# KickTrigger.net
KiCad netlist of a schematic drawn in Altium Designer
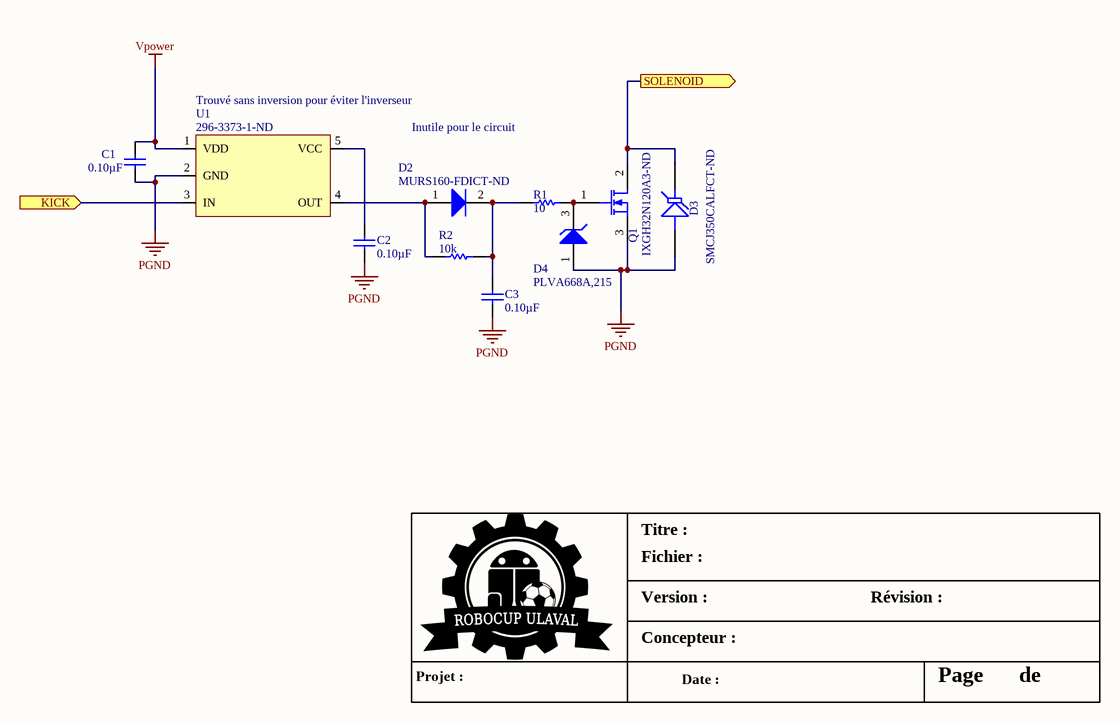
[diagram p0: KickTrigger.SchDoc]

(export (version "E")
  (design (tool "Eeschema 10.0.6"))
  (components
    (comp (ref "C1")
      (value "CL10B104KB8SFNC")
      (footprint "0603")
      (description "CAP CER 0.1UF 50V X7R 0603")
      (fields
        (field (name "MANUFACTURER") "Samsung Electro-Mechanics America, Inc.")
        (field (name "TOLERANCE") "±10%")
        (field (name "CAPACITANCE") "0.10µF")
      )
      (libsource (lib "ResCap") (part "CL10B104KB8SFNC"))
    )
    (comp (ref "C2")
      (value "CL10B104KB8SFNC")
      (footprint "0603")
      (description "CAP CER 0.1UF 50V X7R 0603")
      (fields
        (field (name "MANUFACTURER") "Samsung Electro-Mechanics America, Inc.")
        (field (name "TOLERANCE") "±10%")
        (field (name "CAPACITANCE") "0.10µF")
      )
      (libsource (lib "ResCap") (part "CL10B104KB8SFNC"))
    )
    (comp (ref "C3")
      (value "CL10B104KB8SFNC")
      (footprint "0603")
      (description "CAP CER 0.1UF 50V X7R 0603")
      (fields
        (field (name "MANUFACTURER") "Samsung Electro-Mechanics America, Inc.")
        (field (name "TOLERANCE") "±10%")
        (field (name "CAPACITANCE") "0.10µF")
      )
      (libsource (lib "ResCap") (part "CL10B104KB8SFNC"))
    )
    (comp (ref "D2")
      (value "MURS160-13-F")
      (footprint "SMB")
      (description "DIODE GEN PURP 600V 1A SMB")
      (fields
        (field (name "MANUFACTURER") "Diodes Incorporated")
        (field (name "SUPPLIER PART NUMBER 1") "MURS160-FDICT-ND")
      )
      (libsource (lib "gamma_gestionkicker") (part "MURS160-13-F"))
    )
    (comp (ref "D3")
      (value "SMCJ350CA")
      (footprint "SMC")
      (description "TVS DIODE 350VWM 567VC SMC")
      (fields
        (field (name "MANUFACTURER") "Littelfuse Inc.")
        (field (name "SUPPLIER PART NUMBER 1") "SMCJ350CALFCT-ND")
      )
      (libsource (lib "gamma_gestionkicker") (part "SMCJ350CA"))
    )
    (comp (ref "D4")
      (value "PLVA668A,215")
      (footprint "SOT-23-3")
      (description "DIODE ZENER 6.8V 250MW SOT23")
      (fields (field (name "MANUFACTURER") "NXP Semiconductors") (field (name "TOLERANCE") "±3%"))
      (libsource (lib "gamma_gestionkicker") (part "PLVA668A,215"))
    )
    (comp (ref "Q1")
      (value "IXGH32N120A3")
      (footprint "TO-247 (bent)")
      (description "IGBT 1200V 75A 300W TO247")
      (fields (field (name "MANUFACTURER") "IXYS") (field (name "SUPPLIER PART NUMBER 1") "IXGH32N120A3-ND"))
      (libsource (lib "gamma_gestionkicker") (part "IXGH32N120A3"))
    )
    (comp (ref "R1")
      (value "RC0603FR-0710RL")
      (footprint "0603")
      (description "RES SMD 10 OHM 1% 1/10W 0603")
      (fields
        (field (name "MANUFACTURER") "Yageo")
        (field (name "TOLERANCE") "±1%")
        (field (name "RESISTANCE (OHMS)") "10")
      )
      (libsource (lib "ResCap") (part "RC0603FR-0710RL"))
    )
    (comp (ref "R2")
      (value "RC0603JR-0710KL")
      (footprint "0603")
      (description "RES SMD 10K OHM 5% 1/10W 0603")
      (fields
        (field (name "MANUFACTURER") "Yageo")
        (field (name "TOLERANCE") "±5%")
        (field (name "RESISTANCE (OHMS)") "10k")
      )
      (libsource (lib "ResCap") (part "RC0603JR-0710KL"))
    )
    (comp (ref "U1")
      (value "TPS2818DBVR")
      (footprint "SOT-23-5")
      (description "IC INVERTING FET DRVR SOT-23-5")
      (fields
        (field (name "MANUFACTURER") "Texas Instruments")
        (field (name "SUPPLIER PART NUMBER 1") "296-3373-1-ND")
      )
      (libsource (lib "gamma_gestionkicker") (part "TPS2818DBVR"))
    )
  )
  (nets
    (net (code "1") (name "/KICK") (class "Default")
      (node (ref "U1") (pin "3") (pinfunction "IN_3") (pintype "bidirectional"))
    )
    (net (code "2") (name "/SOLENOID") (class "Default")
      (node (ref "D3") (pin "2") (pinfunction "K_2") (pintype "passive"))
      (node (ref "Q1") (pin "2") (pinfunction "D_2") (pintype "passive"))
    )
    (net (code "3") (name "Net-(D2-A)") (class "Default")
      (node (ref "D2") (pin "1") (pinfunction "A_1") (pintype "passive"))
      (node (ref "R2") (pin "1") (pinfunction "1_1") (pintype "passive"))
      (node (ref "U1") (pin "4") (pinfunction "OUT_4") (pintype "bidirectional"))
    )
    (net (code "4") (name "Net-(D2-K)") (class "Default")
      (node (ref "C3") (pin "2") (pinfunction "2_2") (pintype "passive"))
      (node (ref "D2") (pin "2") (pinfunction "K_2") (pintype "passive"))
      (node (ref "R1") (pin "1") (pinfunction "1_1") (pintype "passive"))
      (node (ref "R2") (pin "2") (pinfunction "2_2") (pintype "passive"))
    )
    (net (code "5") (name "Net-(D4-K)") (class "Default")
      (node (ref "D4") (pin "3") (pinfunction "K_3") (pintype "passive"))
      (node (ref "Q1") (pin "1") (pinfunction "G_1") (pintype "passive"))
      (node (ref "R1") (pin "2") (pinfunction "2_2") (pintype "passive"))
    )
    (net (code "6") (name "Net-(U1-VCC)") (class "Default")
      (node (ref "C2") (pin "2") (pinfunction "2_2") (pintype "passive"))
      (node (ref "U1") (pin "5") (pinfunction "VCC_5") (pintype "bidirectional"))
    )
    (net (code "7") (name "PGND") (class "Default")
      (node (ref "C1") (pin "2") (pinfunction "2_2") (pintype "passive"))
      (node (ref "C2") (pin "1") (pinfunction "1_1") (pintype "passive"))
      (node (ref "C3") (pin "1") (pinfunction "1_1") (pintype "passive"))
      (node (ref "D3") (pin "1") (pinfunction "A_1") (pintype "passive"))
      (node (ref "D4") (pin "1") (pinfunction "A_1") (pintype "passive"))
      (node (ref "Q1") (pin "3") (pinfunction "S_3") (pintype "passive"))
      (node (ref "U1") (pin "2") (pinfunction "GND_2") (pintype "bidirectional"))
    )
    (net (code "8") (name "Vpower") (class "Default")
      (node (ref "C1") (pin "1") (pinfunction "1_1") (pintype "passive"))
      (node (ref "U1") (pin "1") (pinfunction "VDD_1") (pintype "bidirectional"))
    )
  )
)
